# HIVE_BOARD_MCU.net
KiCad netlist of a schematic drawn in Altium Designer
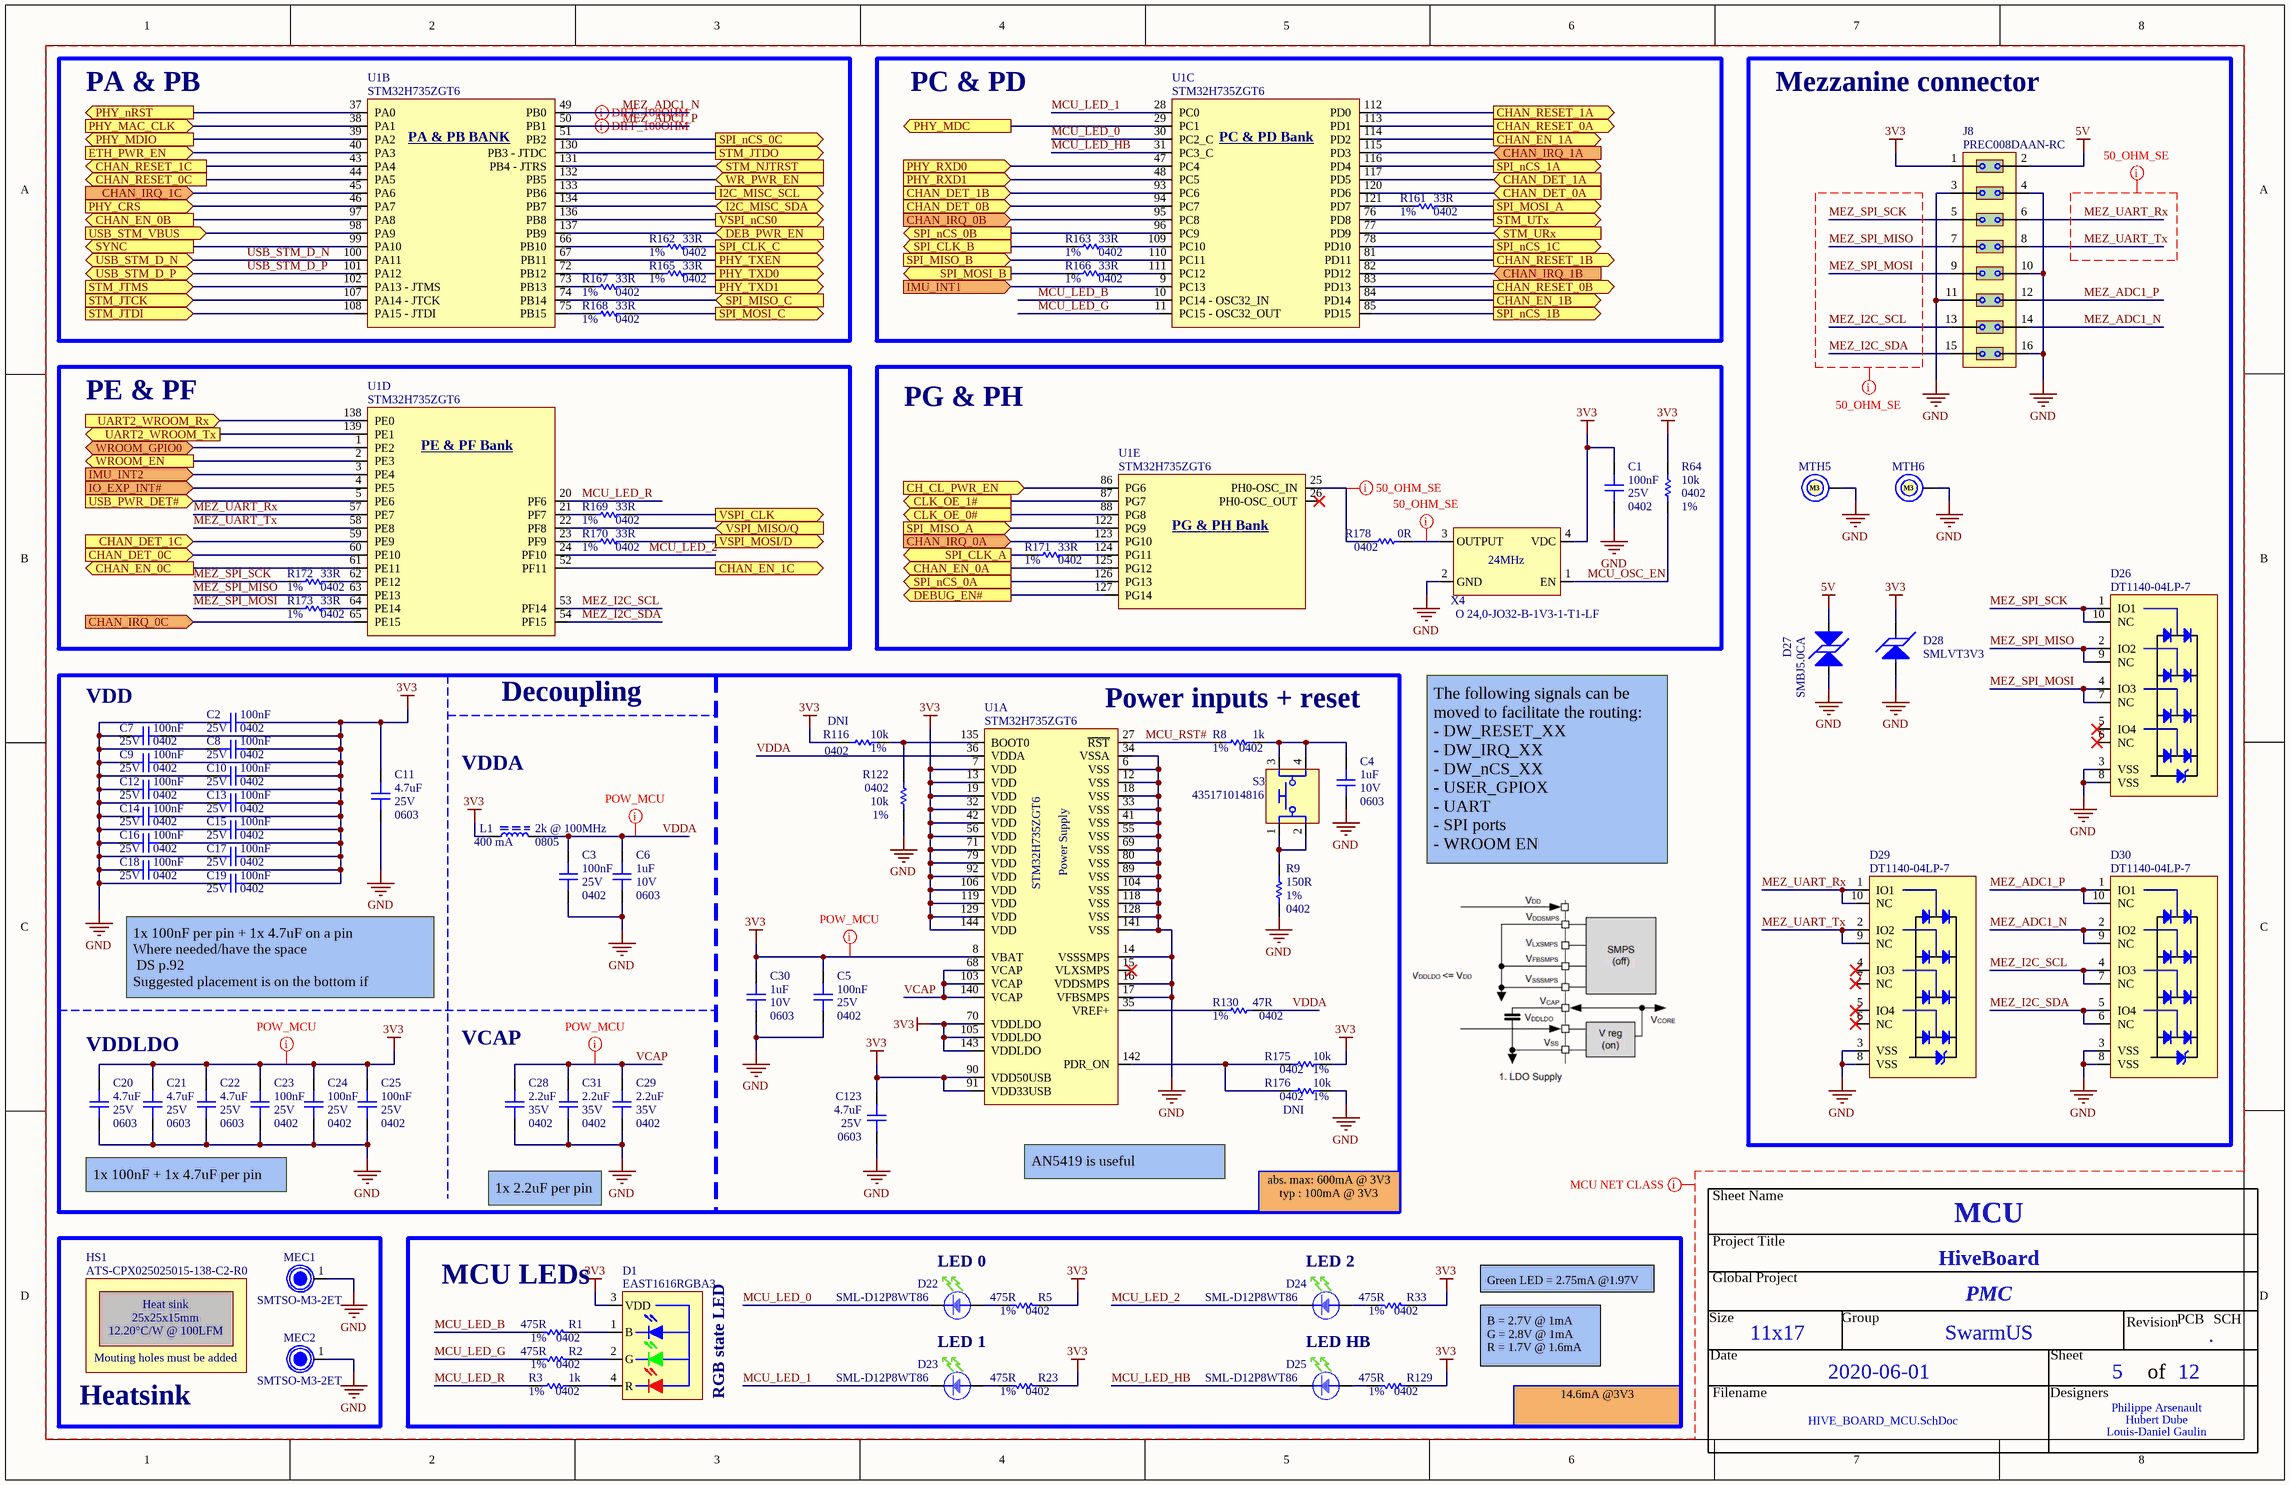
[diagram p0: HIVE_BOARD_MCU.SchDoc]

(export (version "E")
  (design (tool "Eeschema 10.0.6"))
  (components
    (comp (ref "C1")
      (value "100nF")
      (footprint "CAP_CER_0402")
      (description "CAP - CER 0.1µF 10% 25V X7R - 0402")
      (fields
        (field (name "TOLERANCE") "10%")
        (field (name "PACKAGE") "0402")
        (field (name "VOLTAGE RATING") "25V")
        (field (name "Comment") "CGA2B3X7R1E104K050BB")
        (field (name "CREATEDBY/DATE") "Nicolas Roy 2018-11-07")
        (field (name "VERIFIEDBY") "Nicolas V. (2019-01-22)")
      )
      (libsource (lib "GRAMS_MASTER_LIB") (part "CAP_CER_CGA2B3X7R1E104K050BB"))
    )
    (comp (ref "C2")
      (value "100nF")
      (footprint "CAP_CER_0402")
      (description "CAP - CER 0.1µF 10% 25V X7R - 0402")
      (fields
        (field (name "TOLERANCE") "10%")
        (field (name "PACKAGE") "0402")
        (field (name "VOLTAGE RATING") "25V")
        (field (name "Comment") "CGA2B3X7R1E104K050BB")
        (field (name "CREATEDBY/DATE") "Nicolas Roy 2018-11-07")
        (field (name "VERIFIEDBY") "Nicolas V. (2019-01-22)")
      )
      (libsource (lib "GRAMS_MASTER_LIB") (part "CAP_CER_CGA2B3X7R1E104K050BB"))
    )
    (comp (ref "C3")
      (value "100nF")
      (footprint "CAP_CER_0402")
      (description "CAP - CER 0.1µF 10% 25V X7R - 0402")
      (fields
        (field (name "TOLERANCE") "10%")
        (field (name "PACKAGE") "0402")
        (field (name "VOLTAGE RATING") "25V")
        (field (name "Comment") "CGA2B3X7R1E104K050BB")
        (field (name "CREATEDBY/DATE") "Nicolas Roy 2018-11-07")
        (field (name "VERIFIEDBY") "Nicolas V. (2019-01-22)")
      )
      (libsource (lib "GRAMS_MASTER_LIB") (part "CAP_CER_CGA2B3X7R1E104K050BB"))
    )
    (comp (ref "C4")
      (value "1uF")
      (footprint "CAP_CER_0603")
      (description "CAP - CER 1uF 10V 10% X5R - 0603")
      (fields
        (field (name "TOLERANCE") "10%")
        (field (name "PACKAGE") "0603")
        (field (name "VOLTAGE RATING") "10V")
        (field (name "Comment") "C0603C105K8PACTU")
        (field (name "CREATEDBY/DATE") "Hubert Dube - 21/07/20")
        (field (name "VERIFIEDBY") "Louis-Daniel Gaulin - 21/07/20")
      )
      (libsource (lib "SWARMUS_LIB") (part "CAP_CER_C0603C105K8PACTU"))
    )
    (comp (ref "C5")
      (value "100nF")
      (footprint "CAP_CER_0402")
      (description "CAP - CER 0.1µF 10% 25V X7R - 0402")
      (fields
        (field (name "TOLERANCE") "10%")
        (field (name "PACKAGE") "0402")
        (field (name "VOLTAGE RATING") "25V")
        (field (name "Comment") "CGA2B3X7R1E104K050BB")
        (field (name "CREATEDBY/DATE") "Nicolas Roy 2018-11-07")
        (field (name "VERIFIEDBY") "Nicolas V. (2019-01-22)")
      )
      (libsource (lib "GRAMS_MASTER_LIB") (part "CAP_CER_CGA2B3X7R1E104K050BB"))
    )
    (comp (ref "C6")
      (value "1uF")
      (footprint "CAP_CER_0603")
      (description "CAP - CER 1uF 10V 10% X5R - 0603")
      (fields
        (field (name "TOLERANCE") "10%")
        (field (name "PACKAGE") "0603")
        (field (name "VOLTAGE RATING") "10V")
        (field (name "Comment") "C0603C105K8PACTU")
        (field (name "CREATEDBY/DATE") "Hubert Dube - 21/07/20")
        (field (name "VERIFIEDBY") "Louis-Daniel Gaulin - 21/07/20")
      )
      (libsource (lib "SWARMUS_LIB") (part "CAP_CER_C0603C105K8PACTU"))
    )
    (comp (ref "C7")
      (value "100nF")
      (footprint "CAP_CER_0402")
      (description "CAP - CER 0.1µF 10% 25V X7R - 0402")
      (fields
        (field (name "TOLERANCE") "10%")
        (field (name "PACKAGE") "0402")
        (field (name "VOLTAGE RATING") "25V")
        (field (name "Comment") "CGA2B3X7R1E104K050BB")
        (field (name "CREATEDBY/DATE") "Nicolas Roy 2018-11-07")
        (field (name "VERIFIEDBY") "Nicolas V. (2019-01-22)")
      )
      (libsource (lib "GRAMS_MASTER_LIB") (part "CAP_CER_CGA2B3X7R1E104K050BB"))
    )
    (comp (ref "C8")
      (value "100nF")
      (footprint "CAP_CER_0402")
      (description "CAP - CER 0.1µF 10% 25V X7R - 0402")
      (fields
        (field (name "TOLERANCE") "10%")
        (field (name "PACKAGE") "0402")
        (field (name "VOLTAGE RATING") "25V")
        (field (name "Comment") "CGA2B3X7R1E104K050BB")
        (field (name "CREATEDBY/DATE") "Nicolas Roy 2018-11-07")
        (field (name "VERIFIEDBY") "Nicolas V. (2019-01-22)")
      )
      (libsource (lib "GRAMS_MASTER_LIB") (part "CAP_CER_CGA2B3X7R1E104K050BB"))
    )
    (comp (ref "C9")
      (value "100nF")
      (footprint "CAP_CER_0402")
      (description "CAP - CER 0.1µF 10% 25V X7R - 0402")
      (fields
        (field (name "TOLERANCE") "10%")
        (field (name "PACKAGE") "0402")
        (field (name "VOLTAGE RATING") "25V")
        (field (name "Comment") "CGA2B3X7R1E104K050BB")
        (field (name "CREATEDBY/DATE") "Nicolas Roy 2018-11-07")
        (field (name "VERIFIEDBY") "Nicolas V. (2019-01-22)")
      )
      (libsource (lib "GRAMS_MASTER_LIB") (part "CAP_CER_CGA2B3X7R1E104K050BB"))
    )
    (comp (ref "C10")
      (value "100nF")
      (footprint "CAP_CER_0402")
      (description "CAP - CER 0.1µF 10% 25V X7R - 0402")
      (fields
        (field (name "TOLERANCE") "10%")
        (field (name "PACKAGE") "0402")
        (field (name "VOLTAGE RATING") "25V")
        (field (name "Comment") "CGA2B3X7R1E104K050BB")
        (field (name "CREATEDBY/DATE") "Nicolas Roy 2018-11-07")
        (field (name "VERIFIEDBY") "Nicolas V. (2019-01-22)")
      )
      (libsource (lib "GRAMS_MASTER_LIB") (part "CAP_CER_CGA2B3X7R1E104K050BB"))
    )
    (comp (ref "C11")
      (value "4.7uF")
      (footprint "CAP_CER_0603")
      (description "CAP - CER 4.7µF 20% 25V X5R - 0603")
      (fields
        (field (name "TOLERANCE") "20%")
        (field (name "PACKAGE") "0603")
        (field (name "VOLTAGE RATING") "25V")
        (field (name "Comment") "CL10A475MA8NQNC")
        (field (name "CREATEDBY/DATE") "Nicolas Roy 2018-11-21")
        (field (name "VERIFIEDBY") "Nicolas V. (2019-01-22)")
      )
      (libsource (lib "GRAMS_MASTER_LIB") (part "CAP_CER_CL10A475MA8NQNC"))
    )
    (comp (ref "C12")
      (value "100nF")
      (footprint "CAP_CER_0402")
      (description "CAP - CER 0.1µF 10% 25V X7R - 0402")
      (fields
        (field (name "TOLERANCE") "10%")
        (field (name "PACKAGE") "0402")
        (field (name "VOLTAGE RATING") "25V")
        (field (name "Comment") "CGA2B3X7R1E104K050BB")
        (field (name "CREATEDBY/DATE") "Nicolas Roy 2018-11-07")
        (field (name "VERIFIEDBY") "Nicolas V. (2019-01-22)")
      )
      (libsource (lib "GRAMS_MASTER_LIB") (part "CAP_CER_CGA2B3X7R1E104K050BB"))
    )
    (comp (ref "C13")
      (value "100nF")
      (footprint "CAP_CER_0402")
      (description "CAP - CER 0.1µF 10% 25V X7R - 0402")
      (fields
        (field (name "TOLERANCE") "10%")
        (field (name "PACKAGE") "0402")
        (field (name "VOLTAGE RATING") "25V")
        (field (name "Comment") "CGA2B3X7R1E104K050BB")
        (field (name "CREATEDBY/DATE") "Nicolas Roy 2018-11-07")
        (field (name "VERIFIEDBY") "Nicolas V. (2019-01-22)")
      )
      (libsource (lib "GRAMS_MASTER_LIB") (part "CAP_CER_CGA2B3X7R1E104K050BB"))
    )
    (comp (ref "C14")
      (value "100nF")
      (footprint "CAP_CER_0402")
      (description "CAP - CER 0.1µF 10% 25V X7R - 0402")
      (fields
        (field (name "TOLERANCE") "10%")
        (field (name "PACKAGE") "0402")
        (field (name "VOLTAGE RATING") "25V")
        (field (name "Comment") "CGA2B3X7R1E104K050BB")
        (field (name "CREATEDBY/DATE") "Nicolas Roy 2018-11-07")
        (field (name "VERIFIEDBY") "Nicolas V. (2019-01-22)")
      )
      (libsource (lib "GRAMS_MASTER_LIB") (part "CAP_CER_CGA2B3X7R1E104K050BB"))
    )
    (comp (ref "C15")
      (value "100nF")
      (footprint "CAP_CER_0402")
      (description "CAP - CER 0.1µF 10% 25V X7R - 0402")
      (fields
        (field (name "TOLERANCE") "10%")
        (field (name "PACKAGE") "0402")
        (field (name "VOLTAGE RATING") "25V")
        (field (name "Comment") "CGA2B3X7R1E104K050BB")
        (field (name "CREATEDBY/DATE") "Nicolas Roy 2018-11-07")
        (field (name "VERIFIEDBY") "Nicolas V. (2019-01-22)")
      )
      (libsource (lib "GRAMS_MASTER_LIB") (part "CAP_CER_CGA2B3X7R1E104K050BB"))
    )
    (comp (ref "C16")
      (value "100nF")
      (footprint "CAP_CER_0402")
      (description "CAP - CER 0.1µF 10% 25V X7R - 0402")
      (fields
        (field (name "TOLERANCE") "10%")
        (field (name "PACKAGE") "0402")
        (field (name "VOLTAGE RATING") "25V")
        (field (name "Comment") "CGA2B3X7R1E104K050BB")
        (field (name "CREATEDBY/DATE") "Nicolas Roy 2018-11-07")
        (field (name "VERIFIEDBY") "Nicolas V. (2019-01-22)")
      )
      (libsource (lib "GRAMS_MASTER_LIB") (part "CAP_CER_CGA2B3X7R1E104K050BB"))
    )
    (comp (ref "C17")
      (value "100nF")
      (footprint "CAP_CER_0402")
      (description "CAP - CER 0.1µF 10% 25V X7R - 0402")
      (fields
        (field (name "TOLERANCE") "10%")
        (field (name "PACKAGE") "0402")
        (field (name "VOLTAGE RATING") "25V")
        (field (name "Comment") "CGA2B3X7R1E104K050BB")
        (field (name "CREATEDBY/DATE") "Nicolas Roy 2018-11-07")
        (field (name "VERIFIEDBY") "Nicolas V. (2019-01-22)")
      )
      (libsource (lib "GRAMS_MASTER_LIB") (part "CAP_CER_CGA2B3X7R1E104K050BB"))
    )
    (comp (ref "C18")
      (value "100nF")
      (footprint "CAP_CER_0402")
      (description "CAP - CER 0.1µF 10% 25V X7R - 0402")
      (fields
        (field (name "TOLERANCE") "10%")
        (field (name "PACKAGE") "0402")
        (field (name "VOLTAGE RATING") "25V")
        (field (name "Comment") "CGA2B3X7R1E104K050BB")
        (field (name "CREATEDBY/DATE") "Nicolas Roy 2018-11-07")
        (field (name "VERIFIEDBY") "Nicolas V. (2019-01-22)")
      )
      (libsource (lib "GRAMS_MASTER_LIB") (part "CAP_CER_CGA2B3X7R1E104K050BB"))
    )
    (comp (ref "C19")
      (value "100nF")
      (footprint "CAP_CER_0402")
      (description "CAP - CER 0.1µF 10% 25V X7R - 0402")
      (fields
        (field (name "TOLERANCE") "10%")
        (field (name "PACKAGE") "0402")
        (field (name "VOLTAGE RATING") "25V")
        (field (name "Comment") "CGA2B3X7R1E104K050BB")
        (field (name "CREATEDBY/DATE") "Nicolas Roy 2018-11-07")
        (field (name "VERIFIEDBY") "Nicolas V. (2019-01-22)")
      )
      (libsource (lib "GRAMS_MASTER_LIB") (part "CAP_CER_CGA2B3X7R1E104K050BB"))
    )
    (comp (ref "C20")
      (value "4.7uF")
      (footprint "CAP_CER_0603")
      (description "CAP - CER 4.7µF 20% 25V X5R - 0603")
      (fields
        (field (name "TOLERANCE") "20%")
        (field (name "PACKAGE") "0603")
        (field (name "VOLTAGE RATING") "25V")
        (field (name "Comment") "CL10A475MA8NQNC")
        (field (name "CREATEDBY/DATE") "Nicolas Roy 2018-11-21")
        (field (name "VERIFIEDBY") "Nicolas V. (2019-01-22)")
      )
      (libsource (lib "GRAMS_MASTER_LIB") (part "CAP_CER_CL10A475MA8NQNC"))
    )
    (comp (ref "C21")
      (value "4.7uF")
      (footprint "CAP_CER_0603")
      (description "CAP - CER 4.7µF 20% 25V X5R - 0603")
      (fields
        (field (name "TOLERANCE") "20%")
        (field (name "PACKAGE") "0603")
        (field (name "VOLTAGE RATING") "25V")
        (field (name "Comment") "CL10A475MA8NQNC")
        (field (name "CREATEDBY/DATE") "Nicolas Roy 2018-11-21")
        (field (name "VERIFIEDBY") "Nicolas V. (2019-01-22)")
      )
      (libsource (lib "GRAMS_MASTER_LIB") (part "CAP_CER_CL10A475MA8NQNC"))
    )
    (comp (ref "C22")
      (value "4.7uF")
      (footprint "CAP_CER_0603")
      (description "CAP - CER 4.7µF 20% 25V X5R - 0603")
      (fields
        (field (name "TOLERANCE") "20%")
        (field (name "PACKAGE") "0603")
        (field (name "VOLTAGE RATING") "25V")
        (field (name "Comment") "CL10A475MA8NQNC")
        (field (name "CREATEDBY/DATE") "Nicolas Roy 2018-11-21")
        (field (name "VERIFIEDBY") "Nicolas V. (2019-01-22)")
      )
      (libsource (lib "GRAMS_MASTER_LIB") (part "CAP_CER_CL10A475MA8NQNC"))
    )
    (comp (ref "C23")
      (value "100nF")
      (footprint "CAP_CER_0402")
      (description "CAP - CER 0.1µF 10% 25V X7R - 0402")
      (fields
        (field (name "TOLERANCE") "10%")
        (field (name "PACKAGE") "0402")
        (field (name "VOLTAGE RATING") "25V")
        (field (name "Comment") "CGA2B3X7R1E104K050BB")
        (field (name "CREATEDBY/DATE") "Nicolas Roy 2018-11-07")
        (field (name "VERIFIEDBY") "Nicolas V. (2019-01-22)")
      )
      (libsource (lib "GRAMS_MASTER_LIB") (part "CAP_CER_CGA2B3X7R1E104K050BB"))
    )
    (comp (ref "C24")
      (value "100nF")
      (footprint "CAP_CER_0402")
      (description "CAP - CER 0.1µF 10% 25V X7R - 0402")
      (fields
        (field (name "TOLERANCE") "10%")
        (field (name "PACKAGE") "0402")
        (field (name "VOLTAGE RATING") "25V")
        (field (name "Comment") "CGA2B3X7R1E104K050BB")
        (field (name "CREATEDBY/DATE") "Nicolas Roy 2018-11-07")
        (field (name "VERIFIEDBY") "Nicolas V. (2019-01-22)")
      )
      (libsource (lib "GRAMS_MASTER_LIB") (part "CAP_CER_CGA2B3X7R1E104K050BB"))
    )
    (comp (ref "C25")
      (value "100nF")
      (footprint "CAP_CER_0402")
      (description "CAP - CER 0.1µF 10% 25V X7R - 0402")
      (fields
        (field (name "TOLERANCE") "10%")
        (field (name "PACKAGE") "0402")
        (field (name "VOLTAGE RATING") "25V")
        (field (name "Comment") "CGA2B3X7R1E104K050BB")
        (field (name "CREATEDBY/DATE") "Nicolas Roy 2018-11-07")
        (field (name "VERIFIEDBY") "Nicolas V. (2019-01-22)")
      )
      (libsource (lib "GRAMS_MASTER_LIB") (part "CAP_CER_CGA2B3X7R1E104K050BB"))
    )
    (comp (ref "C28")
      (value "2.2uF")
      (footprint "CAP_CER_0402")
      (description "CAP - CER 2.2µF 10% 35V X5R - 0402")
      (fields
        (field (name "TOLERANCE") "10%")
        (field (name "PACKAGE") "0402")
        (field (name "VOLTAGE RATING") "35V")
        (field (name "Comment") "C1005X5R1V225K050BC")
        (field (name "CREATEDBY/DATE") "Nicolas Roy 2018-10-17")
        (field (name "VERIFIEDBY") "Caroline Paulin - 18 janv 2018")
      )
      (libsource (lib "GRAMS_MASTER_LIB") (part "CAP_CER_C1005X5R1V225K050BC"))
    )
    (comp (ref "C29")
      (value "2.2uF")
      (footprint "CAP_CER_0402")
      (description "CAP - CER 2.2µF 10% 35V X5R - 0402")
      (fields
        (field (name "TOLERANCE") "10%")
        (field (name "PACKAGE") "0402")
        (field (name "VOLTAGE RATING") "35V")
        (field (name "Comment") "C1005X5R1V225K050BC")
        (field (name "CREATEDBY/DATE") "Nicolas Roy 2018-10-17")
        (field (name "VERIFIEDBY") "Caroline Paulin - 18 janv 2018")
      )
      (libsource (lib "GRAMS_MASTER_LIB") (part "CAP_CER_C1005X5R1V225K050BC"))
    )
    (comp (ref "C30")
      (value "1uF")
      (footprint "CAP_CER_0603")
      (description "CAP - CER 1uF 10V 10% X5R - 0603")
      (fields
        (field (name "TOLERANCE") "10%")
        (field (name "PACKAGE") "0603")
        (field (name "VOLTAGE RATING") "10V")
        (field (name "Comment") "C0603C105K8PACTU")
        (field (name "CREATEDBY/DATE") "Hubert Dube - 21/07/20")
        (field (name "VERIFIEDBY") "Louis-Daniel Gaulin - 21/07/20")
      )
      (libsource (lib "SWARMUS_LIB") (part "CAP_CER_C0603C105K8PACTU"))
    )
    (comp (ref "C31")
      (value "2.2uF")
      (footprint "CAP_CER_0402")
      (description "CAP - CER 2.2µF 10% 35V X5R - 0402")
      (fields
        (field (name "TOLERANCE") "10%")
        (field (name "PACKAGE") "0402")
        (field (name "VOLTAGE RATING") "35V")
        (field (name "Comment") "C1005X5R1V225K050BC")
        (field (name "CREATEDBY/DATE") "Nicolas Roy 2018-10-17")
        (field (name "VERIFIEDBY") "Caroline Paulin - 18 janv 2018")
      )
      (libsource (lib "GRAMS_MASTER_LIB") (part "CAP_CER_C1005X5R1V225K050BC"))
    )
    (comp (ref "C123")
      (value "4.7uF")
      (footprint "CAP_CER_0603")
      (description "CAP - CER 4.7µF 20% 25V X5R - 0603")
      (fields
        (field (name "TOLERANCE") "20%")
        (field (name "PACKAGE") "0603")
        (field (name "VOLTAGE RATING") "25V")
        (field (name "Comment") "CL10A475MA8NQNC")
        (field (name "CREATEDBY/DATE") "Nicolas Roy 2018-11-21")
        (field (name "VERIFIEDBY") "Nicolas V. (2019-01-22)")
      )
      (libsource (lib "GRAMS_MASTER_LIB") (part "CAP_CER_CL10A475MA8NQNC"))
    )
    (comp (ref "D1")
      (value "EAST1616RGBA3")
      (footprint "DIO_EAST1616RGBA3")
      (fields
        (field (name "TOLERANCE") "±50ppm")
        (field (name "CREATEDBY/DATE") "Hubert Dube - 26/02/2021")
        (field (name "VERIFIEDBY") "PA + Hubert Dube - 19/03/2021")
      )
      (libsource (lib "SWARMUS_LIB") (part "DIO_EAST1616RGBA3"))
    )
    (comp (ref "D22")
      (value "SML-D12P8WT86")
      (footprint "LED_SML-D12P8WT86")
      (description "LED - GREEN DIFFUSED 0603 SMD - 0603")
      (fields
        (field (name "CREATEDBY/DATE") "Keven Deslandes - 2018/11/21")
        (field (name "VERIFIEDBY") "Caroline Paulin - 13 février 2019")
      )
      (libsource (lib "GRAMS_MASTER_LIB") (part "LED_SML-D12P8WT86"))
    )
    (comp (ref "D23")
      (value "SML-D12P8WT86")
      (footprint "LED_SML-D12P8WT86")
      (description "LED - GREEN DIFFUSED 0603 SMD - 0603")
      (fields
        (field (name "CREATEDBY/DATE") "Keven Deslandes - 2018/11/21")
        (field (name "VERIFIEDBY") "Caroline Paulin - 13 février 2019")
      )
      (libsource (lib "GRAMS_MASTER_LIB") (part "LED_SML-D12P8WT86"))
    )
    (comp (ref "D24")
      (value "SML-D12P8WT86")
      (footprint "LED_SML-D12P8WT86")
      (description "LED - GREEN DIFFUSED 0603 SMD - 0603")
      (fields
        (field (name "CREATEDBY/DATE") "Keven Deslandes - 2018/11/21")
        (field (name "VERIFIEDBY") "Caroline Paulin - 13 février 2019")
      )
      (libsource (lib "GRAMS_MASTER_LIB") (part "LED_SML-D12P8WT86"))
    )
    (comp (ref "D25")
      (value "SML-D12P8WT86")
      (footprint "LED_SML-D12P8WT86")
      (description "LED - GREEN DIFFUSED 0603 SMD - 0603")
      (fields
        (field (name "CREATEDBY/DATE") "Keven Deslandes - 2018/11/21")
        (field (name "VERIFIEDBY") "Caroline Paulin - 13 février 2019")
      )
      (libsource (lib "GRAMS_MASTER_LIB") (part "LED_SML-D12P8WT86"))
    )
    (comp (ref "D26")
      (value "DT1140-04LP-7")
      (footprint "TVS_DATA_DT1140-04LP-7")
      (description "TVS - DIODE 5.5V 10V - 10-UFDFN")
      (fields
        (field (name "CREATEDBY/DATE") "Joël Lemay 2019-11-20")
        (field (name "VERIFIEDBY") "C.Paulin - 21/11/2019")
      )
      (libsource (lib "GRAMS_MASTER_LIB") (part "TVS_DATA_DT1140-04LP-7"))
    )
    (comp (ref "D27")
      (value "SMBJ5.0CA")
      (footprint "TVS_PWR_SMBJ5.0CA")
      (description "TVS - BIDIR 5V 9.2V 600W - DO214AA")
      (fields
        (field (name "CREATEDBY/DATE") "Jonathan Bouchard - 2019-03-22")
        (field (name "VERIFIEDBY") "Nicolas V. (2019-05-06)")
      )
      (libsource (lib "GRAMS_MASTER_LIB") (part "TVS_PWR_SMBJ5.0CA"))
    )
    (comp (ref "D28")
      (value "SMLVT3V3")
      (footprint "TVS_POW_SMLVT3V3")
      (description "TVS - 3.3V 10.3V 600W - DO214AA")
      (fields
        (field (name "CREATEDBY/DATE") "Jonathan Bouchard - 2019-04-27")
        (field (name "VERIFIEDBY") "Nicolas V. (2019-05-06)")
      )
      (libsource (lib "GRAMS_MASTER_LIB") (part "TVS_POW_SMLVT3V3"))
    )
    (comp (ref "D29")
      (value "DT1140-04LP-7")
      (footprint "TVS_DATA_DT1140-04LP-7")
      (description "TVS - DIODE 5.5V 10V - 10-UFDFN")
      (fields
        (field (name "CREATEDBY/DATE") "Joël Lemay 2019-11-20")
        (field (name "VERIFIEDBY") "C.Paulin - 21/11/2019")
      )
      (libsource (lib "GRAMS_MASTER_LIB") (part "TVS_DATA_DT1140-04LP-7"))
    )
    (comp (ref "D30")
      (value "DT1140-04LP-7")
      (footprint "TVS_DATA_DT1140-04LP-7")
      (description "TVS - DIODE 5.5V 10V - 10-UFDFN")
      (fields
        (field (name "CREATEDBY/DATE") "Joël Lemay 2019-11-20")
        (field (name "VERIFIEDBY") "C.Paulin - 21/11/2019")
      )
      (libsource (lib "GRAMS_MASTER_LIB") (part "TVS_DATA_DT1140-04LP-7"))
    )
    (comp (ref "HS1")
      (value "ATS-CPX025025015-138-C2-R0")
      (footprint "THE_HS_ATS-CPX025025015-138-C2-R0_NOMH")
      (description "THE_HS - Heat Sink  25x25x15 mm - TH M3")
      (fields
        (field (name "CREATEDBY/DATE") "Philippe Arsenault/2021-04-08")
        (field (name "VERIFIEDBY") "Louis-Daniel Gaulin / 14-04-2021")
      )
      (libsource (lib "SWARMUS_LIB") (part "THE_HS_ATS-CPX025025015-138-C2-R0_NOMH"))
    )
    (comp (ref "J8")
      (value "PREC008DAAN-RC")
      (footprint "CON_HDR_PREC008DAAN-RC")
      (description "CON - Connector Header Through Hole 16 position 0.100\" (2.54mm)")
      (fields
        (field (name "VERIFIEDBY") "Philippe Arsenault/2021-03-25")
        (field (name "CREATEDBY/DATE") "Hubert Dube -  16/03/2021")
      )
      (libsource (lib "SWARMUS_LIB") (part "CON_HDR_PREC008DAAN-RC"))
    )
    (comp (ref "L1")
      (value "2k @ 100MHz")
      (footprint "FER_0805")
      (description "FER - FERRITE BEAD 2 KOHM @ 100 MHz 400 mA - 0805")
      (fields
        (field (name "CURRENT RATING") "400 mA")
        (field (name "PACKAGE") "0805")
        (field (name "Comment") "MMZ2012Y202BT000")
        (field (name "CREATEDBY/DATE") "Hubert Dube - 7/02/2021")
        (field (name "VERIFIEDBY") "Philippe Arsenault/ 2021-03-13")
      )
      (libsource (lib "SWARMUS_LIB") (part "FER_MMZ2012Y202BT000"))
    )
    (comp (ref "MEC1")
      (value "SMTSO-M3-2ET")
      (footprint "MEC_PEM_SMTSO-M3-2ET")
      (description "MEC- PEM SMD THREADED SPACER M3 - SMD")
      (fields
        (field (name "CREATEDBY/DATE") "Gabriel St-H./30-04-2019")
        (field (name "VERIFIEDBY") "Nicolas V. (2019-05-02)")
      )
      (libsource (lib "GRAMS_MASTER_LIB") (part "MEC_PEM_SMTSO-M3-2ET"))
    )
    (comp (ref "MEC2")
      (value "SMTSO-M3-2ET")
      (footprint "MEC_PEM_SMTSO-M3-2ET")
      (description "MEC- PEM SMD THREADED SPACER M3 - SMD")
      (fields
        (field (name "CREATEDBY/DATE") "Gabriel St-H./30-04-2019")
        (field (name "VERIFIEDBY") "Nicolas V. (2019-05-02)")
      )
      (libsource (lib "GRAMS_MASTER_LIB") (part "MEC_PEM_SMTSO-M3-2ET"))
    )
    (comp (ref "MTH5")
      (value "M3")
      (footprint "MTH_M3")
      (description "MTH - MOUNTING HOLE M3 PLATED - M3")
      (fields
        (field (name "CREATEDBY/DATE") "Jonathan Bouchard 2018-07-23")
        (field (name "VERIFIEDBY") "Arnaud Samson 23-07-18")
      )
      (libsource (lib "GRAMS_MASTER_LIB") (part "MTH_M3"))
    )
    (comp (ref "MTH6")
      (value "M3")
      (footprint "MTH_M3")
      (description "MTH - MOUNTING HOLE M3 PLATED - M3")
      (fields
        (field (name "CREATEDBY/DATE") "Jonathan Bouchard 2018-07-23")
        (field (name "VERIFIEDBY") "Arnaud Samson 23-07-18")
      )
      (libsource (lib "GRAMS_MASTER_LIB") (part "MTH_M3"))
    )
    (comp (ref "R1")
      (value "475R")
      (footprint "RES_0402")
      (description "RES - 475R 1% 1/10W- 0402")
      (fields
        (field (name "TOLERANCE") "1%")
        (field (name "PACKAGE") "0402")
        (field (name "Comment") "ERJ-2RKF4750X")
        (field (name "CREATEDBY/DATE") "Keven Deslandes 2018-10-17")
        (field (name "VERIFIEDBY") "Carolilne Paulin - 18/12/2018")
      )
      (libsource (lib "GRAMS_MASTER_LIB") (part "RES_ERJ-2RKF4750X"))
    )
    (comp (ref "R2")
      (value "475R")
      (footprint "RES_0402")
      (description "RES - 475R 1% 1/10W- 0402")
      (fields
        (field (name "TOLERANCE") "1%")
        (field (name "PACKAGE") "0402")
        (field (name "Comment") "ERJ-2RKF4750X")
        (field (name "CREATEDBY/DATE") "Keven Deslandes 2018-10-17")
        (field (name "VERIFIEDBY") "Carolilne Paulin - 18/12/2018")
      )
      (libsource (lib "GRAMS_MASTER_LIB") (part "RES_ERJ-2RKF4750X"))
    )
    (comp (ref "R3")
      (value "1k")
      (footprint "RES_0402")
      (description "RES - 1K OHM 1% 1/16W - 0402")
      (fields
        (field (name "TOLERANCE") "1%")
        (field (name "PACKAGE") "0402")
        (field (name "Comment") "RC0402FR-071KL")
        (field (name "CREATEDBY/DATE") "Jonathan Bouchard 2018-07-05")
        (field (name "VERIFIEDBY") "Arnaud Samson 16-07-18")
      )
      (libsource (lib "GRAMS_MASTER_LIB") (part "RES_RC0402FR-071KL"))
    )
    (comp (ref "R5")
      (value "475R")
      (footprint "RES_0402")
      (description "RES - 475R 1% 1/10W- 0402")
      (fields
        (field (name "TOLERANCE") "1%")
        (field (name "PACKAGE") "0402")
        (field (name "Comment") "ERJ-2RKF4750X")
        (field (name "CREATEDBY/DATE") "Keven Deslandes 2018-10-17")
        (field (name "VERIFIEDBY") "Carolilne Paulin - 18/12/2018")
      )
      (libsource (lib "GRAMS_MASTER_LIB") (part "RES_ERJ-2RKF4750X"))
    )
    (comp (ref "R8")
      (value "1k")
      (footprint "RES_0402")
      (description "RES - 1K OHM 1% 1/16W - 0402")
      (fields
        (field (name "TOLERANCE") "1%")
        (field (name "PACKAGE") "0402")
        (field (name "Comment") "RC0402FR-071KL")
        (field (name "CREATEDBY/DATE") "Jonathan Bouchard 2018-07-05")
        (field (name "VERIFIEDBY") "Arnaud Samson 16-07-18")
      )
      (libsource (lib "GRAMS_MASTER_LIB") (part "RES_RC0402FR-071KL"))
    )
    (comp (ref "R9")
      (value "150R")
      (footprint "RES_0402")
      (description "RES - 150R 1% 1/16W - 0402")
      (fields
        (field (name "TOLERANCE") "1%")
        (field (name "PACKAGE") "0402")
        (field (name "Comment") "RC0402FR-07150RL")
        (field (name "CREATEDBY/DATE") "Jonathan Bouchard 2019-03-25")
        (field (name "VERIFIEDBY") "Nicolas V. (2019-05-02)")
      )
      (libsource (lib "GRAMS_MASTER_LIB") (part "RES_RC0402FR-07150RL"))
    )
    (comp (ref "R23")
      (value "475R")
      (footprint "RES_0402")
      (description "RES - 475R 1% 1/10W- 0402")
      (fields
        (field (name "TOLERANCE") "1%")
        (field (name "PACKAGE") "0402")
        (field (name "Comment") "ERJ-2RKF4750X")
        (field (name "CREATEDBY/DATE") "Keven Deslandes 2018-10-17")
        (field (name "VERIFIEDBY") "Carolilne Paulin - 18/12/2018")
      )
      (libsource (lib "GRAMS_MASTER_LIB") (part "RES_ERJ-2RKF4750X"))
    )
    (comp (ref "R33")
      (value "475R")
      (footprint "RES_0402")
      (description "RES - 475R 1% 1/10W- 0402")
      (fields
        (field (name "TOLERANCE") "1%")
        (field (name "PACKAGE") "0402")
        (field (name "Comment") "ERJ-2RKF4750X")
        (field (name "CREATEDBY/DATE") "Keven Deslandes 2018-10-17")
        (field (name "VERIFIEDBY") "Carolilne Paulin - 18/12/2018")
      )
      (libsource (lib "GRAMS_MASTER_LIB") (part "RES_ERJ-2RKF4750X"))
    )
    (comp (ref "R64")
      (value "10k")
      (footprint "RES_0402")
      (description "RES - 10K OHMS 1% 1/16W - 0402")
      (fields
        (field (name "TOLERANCE") "1%")
        (field (name "PACKAGE") "0402")
        (field (name "Comment") "RC0402FR-0710KL")
        (field (name "CREATEDBY/DATE") "Nicolas V. (2018-11-20)")
        (field (name "VERIFIEDBY") "Nicolas V. (2018-11-20)")
      )
      (libsource (lib "GRAMS_MASTER_LIB") (part "RES_RC0402FR-0710KL"))
    )
    (comp (ref "R116")
      (value "10k")
      (footprint "RES_0402")
      (description "RES - 10K OHMS 1% 1/16W - 0402")
      (fields
        (field (name "TOLERANCE") "1%")
        (field (name "ASSEMBLY NOTE") "DNI")
        (field (name "PACKAGE") "0402")
        (field (name "Comment") "RC0402FR-0710KL")
        (field (name "CREATEDBY/DATE") "Nicolas V. (2018-11-20)")
        (field (name "VERIFIEDBY") "Nicolas V. (2018-11-20)")
      )
      (libsource (lib "GRAMS_MASTER_LIB") (part "RES_RC0402FR-0710KL"))
    )
    (comp (ref "R122")
      (value "10k")
      (footprint "RES_0402")
      (description "RES - 10K OHMS 1% 1/16W - 0402")
      (fields
        (field (name "TOLERANCE") "1%")
        (field (name "PACKAGE") "0402")
        (field (name "Comment") "RC0402FR-0710KL")
        (field (name "CREATEDBY/DATE") "Nicolas V. (2018-11-20)")
        (field (name "VERIFIEDBY") "Nicolas V. (2018-11-20)")
      )
      (libsource (lib "GRAMS_MASTER_LIB") (part "RES_RC0402FR-0710KL"))
    )
    (comp (ref "R129")
      (value "475R")
      (footprint "RES_0402")
      (description "RES - 475R 1% 1/10W- 0402")
      (fields
        (field (name "TOLERANCE") "1%")
        (field (name "PACKAGE") "0402")
        (field (name "Comment") "ERJ-2RKF4750X")
        (field (name "CREATEDBY/DATE") "Keven Deslandes 2018-10-17")
        (field (name "VERIFIEDBY") "Carolilne Paulin - 18/12/2018")
      )
      (libsource (lib "GRAMS_MASTER_LIB") (part "RES_ERJ-2RKF4750X"))
    )
    (comp (ref "R130")
      (value "47R")
      (footprint "RES_0402")
      (description "RES -  47ohm ±1% 0.063W, 1/16W Chip Resistor 0402")
      (fields
        (field (name "TOLERANCE") "1%")
        (field (name "PACKAGE") "0402")
        (field (name "Comment") "RC0402FR-0747RL")
        (field (name "CREATEDBY/DATE") "Philippe Arsenault/2021-04-10")
        (field (name "VERIFIEDBY") "Louis-Daniel Gaulin / 14-04-2021")
      )
      (libsource (lib "SWARMUS_LIB") (part "RES_RC0402FR-0747RL"))
    )
    (comp (ref "R161")
      (value "33R")
      (footprint "RES_0402")
      (description "RES - 33 OHM 1% 1/16W - 0402")
      (fields
        (field (name "TOLERANCE") "1%")
        (field (name "PACKAGE") "0402")
        (field (name "Comment") "RC0402FR-0733RL")
        (field (name "CREATEDBY/DATE") "Louis-Daniel Gaulin/ 14/01/2020")
        (field (name "VERIFIEDBY") "C.Paulin - 21/01/2020")
      )
      (libsource (lib "GRAMS_MASTER_LIB") (part "RES_RC0402FR-0733RL"))
    )
    (comp (ref "R162")
      (value "33R")
      (footprint "RES_0402")
      (description "RES - 33 OHM 1% 1/16W - 0402")
      (fields
        (field (name "TOLERANCE") "1%")
        (field (name "PACKAGE") "0402")
        (field (name "Comment") "RC0402FR-0733RL")
        (field (name "CREATEDBY/DATE") "Louis-Daniel Gaulin/ 14/01/2020")
        (field (name "VERIFIEDBY") "C.Paulin - 21/01/2020")
      )
      (libsource (lib "GRAMS_MASTER_LIB") (part "RES_RC0402FR-0733RL"))
    )
    (comp (ref "R163")
      (value "33R")
      (footprint "RES_0402")
      (description "RES - 33 OHM 1% 1/16W - 0402")
      (fields
        (field (name "TOLERANCE") "1%")
        (field (name "PACKAGE") "0402")
        (field (name "Comment") "RC0402FR-0733RL")
        (field (name "CREATEDBY/DATE") "Louis-Daniel Gaulin/ 14/01/2020")
        (field (name "VERIFIEDBY") "C.Paulin - 21/01/2020")
      )
      (libsource (lib "GRAMS_MASTER_LIB") (part "RES_RC0402FR-0733RL"))
    )
    (comp (ref "R165")
      (value "33R")
      (footprint "RES_0402")
      (description "RES - 33 OHM 1% 1/16W - 0402")
      (fields
        (field (name "TOLERANCE") "1%")
        (field (name "PACKAGE") "0402")
        (field (name "Comment") "RC0402FR-0733RL")
        (field (name "CREATEDBY/DATE") "Louis-Daniel Gaulin/ 14/01/2020")
        (field (name "VERIFIEDBY") "C.Paulin - 21/01/2020")
      )
      (libsource (lib "GRAMS_MASTER_LIB") (part "RES_RC0402FR-0733RL"))
    )
    (comp (ref "R166")
      (value "33R")
      (footprint "RES_0402")
      (description "RES - 33 OHM 1% 1/16W - 0402")
      (fields
        (field (name "TOLERANCE") "1%")
        (field (name "PACKAGE") "0402")
        (field (name "Comment") "RC0402FR-0733RL")
        (field (name "CREATEDBY/DATE") "Louis-Daniel Gaulin/ 14/01/2020")
        (field (name "VERIFIEDBY") "C.Paulin - 21/01/2020")
      )
      (libsource (lib "GRAMS_MASTER_LIB") (part "RES_RC0402FR-0733RL"))
    )
    (comp (ref "R167")
      (value "33R")
      (footprint "RES_0402")
      (description "RES - 33 OHM 1% 1/16W - 0402")
      (fields
        (field (name "TOLERANCE") "1%")
        (field (name "PACKAGE") "0402")
        (field (name "Comment") "RC0402FR-0733RL")
        (field (name "CREATEDBY/DATE") "Louis-Daniel Gaulin/ 14/01/2020")
        (field (name "VERIFIEDBY") "C.Paulin - 21/01/2020")
      )
      (libsource (lib "GRAMS_MASTER_LIB") (part "RES_RC0402FR-0733RL"))
    )
    (comp (ref "R168")
      (value "33R")
      (footprint "RES_0402")
      (description "RES - 33 OHM 1% 1/16W - 0402")
      (fields
        (field (name "TOLERANCE") "1%")
        (field (name "PACKAGE") "0402")
        (field (name "Comment") "RC0402FR-0733RL")
        (field (name "CREATEDBY/DATE") "Louis-Daniel Gaulin/ 14/01/2020")
        (field (name "VERIFIEDBY") "C.Paulin - 21/01/2020")
      )
      (libsource (lib "GRAMS_MASTER_LIB") (part "RES_RC0402FR-0733RL"))
    )
    (comp (ref "R169")
      (value "33R")
      (footprint "RES_0402")
      (description "RES - 33 OHM 1% 1/16W - 0402")
      (fields
        (field (name "TOLERANCE") "1%")
        (field (name "PACKAGE") "0402")
        (field (name "Comment") "RC0402FR-0733RL")
        (field (name "CREATEDBY/DATE") "Louis-Daniel Gaulin/ 14/01/2020")
        (field (name "VERIFIEDBY") "C.Paulin - 21/01/2020")
      )
      (libsource (lib "GRAMS_MASTER_LIB") (part "RES_RC0402FR-0733RL"))
    )
    (comp (ref "R170")
      (value "33R")
      (footprint "RES_0402")
      (description "RES - 33 OHM 1% 1/16W - 0402")
      (fields
        (field (name "TOLERANCE") "1%")
        (field (name "PACKAGE") "0402")
        (field (name "Comment") "RC0402FR-0733RL")
        (field (name "CREATEDBY/DATE") "Louis-Daniel Gaulin/ 14/01/2020")
        (field (name "VERIFIEDBY") "C.Paulin - 21/01/2020")
      )
      (libsource (lib "GRAMS_MASTER_LIB") (part "RES_RC0402FR-0733RL"))
    )
    (comp (ref "R171")
      (value "33R")
      (footprint "RES_0402")
      (description "RES - 33 OHM 1% 1/16W - 0402")
      (fields
        (field (name "TOLERANCE") "1%")
        (field (name "PACKAGE") "0402")
        (field (name "Comment") "RC0402FR-0733RL")
        (field (name "CREATEDBY/DATE") "Louis-Daniel Gaulin/ 14/01/2020")
        (field (name "VERIFIEDBY") "C.Paulin - 21/01/2020")
      )
      (libsource (lib "GRAMS_MASTER_LIB") (part "RES_RC0402FR-0733RL"))
    )
    (comp (ref "R172")
      (value "33R")
      (footprint "RES_0402")
      (description "RES - 33 OHM 1% 1/16W - 0402")
      (fields
        (field (name "TOLERANCE") "1%")
        (field (name "PACKAGE") "0402")
        (field (name "Comment") "RC0402FR-0733RL")
        (field (name "CREATEDBY/DATE") "Louis-Daniel Gaulin/ 14/01/2020")
        (field (name "VERIFIEDBY") "C.Paulin - 21/01/2020")
      )
      (libsource (lib "GRAMS_MASTER_LIB") (part "RES_RC0402FR-0733RL"))
    )
    (comp (ref "R173")
      (value "33R")
      (footprint "RES_0402")
      (description "RES - 33 OHM 1% 1/16W - 0402")
      (fields
        (field (name "TOLERANCE") "1%")
        (field (name "PACKAGE") "0402")
        (field (name "Comment") "RC0402FR-0733RL")
        (field (name "CREATEDBY/DATE") "Louis-Daniel Gaulin/ 14/01/2020")
        (field (name "VERIFIEDBY") "C.Paulin - 21/01/2020")
      )
      (libsource (lib "GRAMS_MASTER_LIB") (part "RES_RC0402FR-0733RL"))
    )
    (comp (ref "R175")
      (value "10k")
      (footprint "RES_0402")
      (description "RES - 10K OHMS 1% 1/16W - 0402")
      (fields
        (field (name "TOLERANCE") "1%")
        (field (name "PACKAGE") "0402")
        (field (name "Comment") "RC0402FR-0710KL")
        (field (name "CREATEDBY/DATE") "Nicolas V. (2018-11-20)")
        (field (name "VERIFIEDBY") "Nicolas V. (2018-11-20)")
      )
      (libsource (lib "GRAMS_MASTER_LIB") (part "RES_RC0402FR-0710KL"))
    )
    (comp (ref "R176")
      (value "10k")
      (footprint "RES_0402")
      (description "RES - 10K OHMS 1% 1/16W - 0402")
      (fields
        (field (name "TOLERANCE") "1%")
        (field (name "ASSEMBLY NOTE") "DNI")
        (field (name "PACKAGE") "0402")
        (field (name "Comment") "RC0402FR-0710KL")
        (field (name "CREATEDBY/DATE") "Nicolas V. (2018-11-20)")
        (field (name "VERIFIEDBY") "Nicolas V. (2018-11-20)")
      )
      (libsource (lib "GRAMS_MASTER_LIB") (part "RES_RC0402FR-0710KL"))
    )
    (comp (ref "R178")
      (value "0R")
      (footprint "RES_0402")
      (description "RES - 0R 1/16W 1A  - 0402")
      (fields
        (field (name "PACKAGE") "0402")
        (field (name "Comment") "RC0402FR-070RL")
        (field (name "CREATEDBY/DATE") "Keven Deslandes 2018-09-12")
        (field (name "VERIFIEDBY") "Caroline Paulin - 27 fév 2019")
      )
      (libsource (lib "GRAMS_MASTER_LIB") (part "RES_RC0402FR-070RL"))
    )
    (comp (ref "S3")
      (value "435171014816")
      (footprint "SWI_TACT_435171014816")
      (description "SWI - SWITCH TACTILE SPST-NO 0.05A 12V -SMD")
      (fields
        (field (name "CREATEDBY/DATE") "Hubert Dube - 22/07/20")
        (field (name "VERIFIEDBY") "Louis-Daniel Gaulin / 12-11-2020")
      )
      (libsource (lib "SWARMUS_LIB") (part "SWI_TACT_435171014816"))
    )
    (comp (ref "U1")
      (value "STM32H735ZGT6")
      (footprint "MCU_STM32H735ZGT6")
      (fields
        (field (name "CREATEDBY/DATE") "Philippe Arsenault/2021-04-08")
        (field (name "VERIFIEDBY") "Louis-Daniel Gaulin / 08-04-2021")
      )
      (libsource (lib "SWARMUS_LIB") (part "MCU_STM32H735ZGT6"))
    )
    (comp (ref "X4")
      (value "O 24,0-JO32-B-1V3-1-T1-LF")
      (footprint "OSC_O 24,0-JO32-B-1V3-1-T1-LF")
      (description "OSC - 24MHz XO (Standard) LVCMOS Oscillator 1.8V ~ 3.3V Enable/Disable 4-SMD, No Lead")
      (fields
        (field (name "TOLERANCE") "±50ppm")
        (field (name "CREATEDBY/DATE") "Louis-Daniel Gaulin / 13-04-2021")
        (field (name "VERIFIEDBY") "Philippe Arsenault/2021-04-14")
      )
      (libsource (lib "SWARMUS_LIB") (part "OSC_O 24,0-JO32-B-1V3-1-T1-LF"))
    )
  )
  (nets
    (net (code "1") (name "/CHAN_DET_0A") (class "Default")
      (node (ref "U1") (pin "120") (pinfunction "PD6_120") (pintype "passive"))
    )
    (net (code "2") (name "/CHAN_DET_0B") (class "Default")
      (node (ref "U1") (pin "94") (pinfunction "PC7_94") (pintype "passive"))
    )
    (net (code "3") (name "/CHAN_DET_0C") (class "Default")
      (node (ref "U1") (pin "60") (pinfunction "PE10_60") (pintype "passive"))
    )
    (net (code "4") (name "/CHAN_DET_1A") (class "Default")
      (node (ref "U1") (pin "117") (pinfunction "PD5_117") (pintype "passive"))
    )
    (net (code "5") (name "/CHAN_DET_1B") (class "Default")
      (node (ref "U1") (pin "93") (pinfunction "PC6_93") (pintype "passive"))
    )
    (net (code "6") (name "/CHAN_DET_1C") (class "Default")
      (node (ref "U1") (pin "59") (pinfunction "PE9_59") (pintype "passive"))
    )
    (net (code "7") (name "/CHAN_EN_0A") (class "Default")
      (node (ref "U1") (pin "125") (pinfunction "PG12_125") (pintype "passive"))
    )
    (net (code "8") (name "/CHAN_EN_0B") (class "Default")
      (node (ref "U1") (pin "97") (pinfunction "PA8_97") (pintype "passive"))
    )
    (net (code "9") (name "/CHAN_EN_0C") (class "Default")
      (node (ref "U1") (pin "61") (pinfunction "PE11_61") (pintype "passive"))
    )
    (net (code "10") (name "/CHAN_EN_1A") (class "Default")
      (node (ref "U1") (pin "114") (pinfunction "PD2_114") (pintype "passive"))
    )
    (net (code "11") (name "/CHAN_EN_1B") (class "Default")
      (node (ref "U1") (pin "84") (pinfunction "PD14_84") (pintype "passive"))
    )
    (net (code "12") (name "/CHAN_EN_1C") (class "Default")
      (node (ref "U1") (pin "52") (pinfunction "PF11_52") (pintype "passive"))
    )
    (net (code "13") (name "/CHAN_IRQ_0A") (class "Default")
      (node (ref "U1") (pin "123") (pinfunction "PG10_123") (pintype "passive"))
    )
    (net (code "14") (name "/CHAN_IRQ_0B") (class "Default")
      (node (ref "U1") (pin "95") (pinfunction "PC8_95") (pintype "passive"))
    )
    (net (code "15") (name "/CHAN_IRQ_0C") (class "Default")
      (node (ref "U1") (pin "65") (pinfunction "PE15_65") (pintype "passive"))
    )
    (net (code "16") (name "/CHAN_IRQ_1A") (class "Default")
      (node (ref "U1") (pin "115") (pinfunction "PD3_115") (pintype "passive"))
    )
    (net (code "17") (name "/CHAN_IRQ_1B") (class "Default")
      (node (ref "U1") (pin "82") (pinfunction "PD12_82") (pintype "passive"))
    )
    (net (code "18") (name "/CHAN_IRQ_1C") (class "Default")
      (node (ref "U1") (pin "45") (pinfunction "PA6_45") (pintype "passive"))
    )
    (net (code "19") (name "/CHAN_RESET_0A") (class "Default")
      (node (ref "U1") (pin "113") (pinfunction "PD1_113") (pintype "passive"))
    )
    (net (code "20") (name "/CHAN_RESET_0B") (class "Default")
      (node (ref "U1") (pin "83") (pinfunction "PD13_83") (pintype "passive"))
    )
    (net (code "21") (name "/CHAN_RESET_0C") (class "Default")
      (node (ref "U1") (pin "44") (pinfunction "PA5_44") (pintype "passive"))
    )
    (net (code "22") (name "/CHAN_RESET_1A") (class "Default")
      (node (ref "U1") (pin "112") (pinfunction "PD0_112") (pintype "passive"))
    )
    (net (code "23") (name "/CHAN_RESET_1B") (class "Default")
      (node (ref "U1") (pin "81") (pinfunction "PD11_81") (pintype "passive"))
    )
    (net (code "24") (name "/CHAN_RESET_1C") (class "Default")
      (node (ref "U1") (pin "43") (pinfunction "PA4_43") (pintype "passive"))
    )
    (net (code "25") (name "/CH_CL_PWR_EN") (class "Default")
      (node (ref "U1") (pin "86") (pinfunction "PG6_86") (pintype "passive"))
    )
    (net (code "26") (name "/CLK_OE_0#") (class "Default")
      (node (ref "U1") (pin "88") (pinfunction "PG8_88") (pintype "passive"))
    )
    (net (code "27") (name "/CLK_OE_1#") (class "Default")
      (node (ref "U1") (pin "87") (pinfunction "PG7_87") (pintype "passive"))
    )
    (net (code "28") (name "/DEBUG_EN#") (class "Default")
      (node (ref "U1") (pin "127") (pinfunction "PG14_127") (pintype "passive"))
    )
    (net (code "29") (name "/DEB_PWR_EN") (class "Default")
      (node (ref "U1") (pin "137") (pinfunction "PB9_137") (pintype "passive"))
    )
    (net (code "30") (name "/ETH_PWR_EN") (class "Default")
      (node (ref "U1") (pin "40") (pinfunction "PA3_40") (pintype "passive"))
    )
    (net (code "31") (name "/I2C_MISC_SCL") (class "Default")
      (node (ref "U1") (pin "133") (pinfunction "PB6_133") (pintype "passive"))
    )
    (net (code "32") (name "/I2C_MISC_SDA") (class "Default")
      (node (ref "U1") (pin "134") (pinfunction "PB7_134") (pintype "passive"))
    )
    (net (code "33") (name "/IMU_INT1") (class "Default")
      (node (ref "U1") (pin "9") (pinfunction "PC13_9") (pintype "passive"))
    )
    (net (code "34") (name "/IMU_INT2") (class "Default")
      (node (ref "U1") (pin "3") (pinfunction "PE4_3") (pintype "passive"))
    )
    (net (code "35") (name "/IO_EXP_INT#") (class "Default")
      (node (ref "U1") (pin "4") (pinfunction "PE5_4") (pintype "passive"))
    )
    (net (code "36") (name "/MCU_LED_0") (class "Default")
      (node (ref "D22") (pin "K") (pinfunction "K_K") (pintype "passive"))
      (node (ref "U1") (pin "30") (pinfunction "PC2_C_30") (pintype "passive"))
    )
    (net (code "37") (name "/MCU_LED_1") (class "Default")
      (node (ref "D23") (pin "K") (pinfunction "K_K") (pintype "passive"))
      (node (ref "U1") (pin "28") (pinfunction "PC0_28") (pintype "passive"))
    )
    (net (code "38") (name "/MCU_LED_2") (class "Default")
      (node (ref "D24") (pin "K") (pinfunction "K_K") (pintype "passive"))
      (node (ref "U1") (pin "24") (pinfunction "PF10_24") (pintype "passive"))
    )
    (net (code "39") (name "/MCU_LED_B") (class "Default")
      (node (ref "R1") (pin "2") (pinfunction "2_2") (pintype "passive"))
      (node (ref "U1") (pin "10") (pinfunction "PC14_-_OSC32_IN_10") (pintype "passive"))
    )
    (net (code "40") (name "/MCU_LED_G") (class "Default")
      (node (ref "R2") (pin "2") (pinfunction "2_2") (pintype "passive"))
      (node (ref "U1") (pin "11") (pinfunction "PC15_-_OSC32_OUT_11") (pintype "passive"))
    )
    (net (code "41") (name "/MCU_LED_HB") (class "Default")
      (node (ref "D25") (pin "K") (pinfunction "K_K") (pintype "passive"))
      (node (ref "U1") (pin "31") (pinfunction "PC3_C_31") (pintype "passive"))
    )
    (net (code "42") (name "/MCU_LED_R") (class "Default")
      (node (ref "R3") (pin "2") (pinfunction "2_2") (pintype "passive"))
      (node (ref "U1") (pin "20") (pinfunction "PF6_20") (pintype "passive"))
    )
    (net (code "43") (name "/MCU_OSC_EN") (class "Default")
      (node (ref "R64") (pin "2") (pinfunction "2_2") (pintype "passive"))
      (node (ref "X4") (pin "1") (pinfunction "EN_1") (pintype "passive"))
    )
    (net (code "44") (name "/MCU_RST#") (class "Default")
      (node (ref "R8") (pin "2") (pinfunction "2_2") (pintype "passive"))
      (node (ref "U1") (pin "27") (pinfunction "RST_27") (pintype "passive"))
    )
    (net (code "45") (name "/MEZ_ADC1_N") (class "Default")
      (node (ref "D30") (pin "2") (pinfunction "IO2_2") (pintype "passive"))
      (node (ref "D30") (pin "9") (pinfunction "NC_9") (pintype "passive"))
      (node (ref "J8") (pin "14") (pintype "passive"))
      (node (ref "U1") (pin "49") (pinfunction "PB0_49") (pintype "passive"))
    )
    (net (code "46") (name "/MEZ_ADC1_P") (class "Default")
      (node (ref "D30") (pin "1") (pinfunction "IO1_1") (pintype "passive"))
      (node (ref "D30") (pin "10") (pinfunction "NC_10") (pintype "passive"))
      (node (ref "J8") (pin "12") (pintype "passive"))
      (node (ref "U1") (pin "50") (pinfunction "PB1_50") (pintype "passive"))
    )
    (net (code "47") (name "/MEZ_I2C_SCL") (class "Default")
      (node (ref "D30") (pin "4") (pinfunction "IO3_4") (pintype "passive"))
      (node (ref "D30") (pin "7") (pinfunction "NC_7") (pintype "passive"))
      (node (ref "J8") (pin "13") (pintype "passive"))
      (node (ref "U1") (pin "53") (pinfunction "PF14_53") (pintype "passive"))
    )
    (net (code "48") (name "/MEZ_I2C_SDA") (class "Default")
      (node (ref "D30") (pin "5") (pinfunction "IO4_5") (pintype "passive"))
      (node (ref "D30") (pin "6") (pinfunction "NC_6") (pintype "passive"))
      (node (ref "J8") (pin "15") (pintype "passive"))
      (node (ref "U1") (pin "54") (pinfunction "PF15_54") (pintype "passive"))
    )
    (net (code "49") (name "/MEZ_SPI_MISO") (class "Default")
      (node (ref "D26") (pin "2") (pinfunction "IO2_2") (pintype "passive"))
      (node (ref "D26") (pin "9") (pinfunction "NC_9") (pintype "passive"))
      (node (ref "J8") (pin "7") (pintype "passive"))
      (node (ref "U1") (pin "63") (pinfunction "PE13_63") (pintype "passive"))
    )
    (net (code "50") (name "/MEZ_SPI_MOSI") (class "Default")
      (node (ref "D26") (pin "4") (pinfunction "IO3_4") (pintype "passive"))
      (node (ref "D26") (pin "7") (pinfunction "NC_7") (pintype "passive"))
      (node (ref "J8") (pin "9") (pintype "passive"))
      (node (ref "R173") (pin "2") (pinfunction "2_2") (pintype "passive"))
    )
    (net (code "51") (name "/MEZ_SPI_SCK") (class "Default")
      (node (ref "D26") (pin "1") (pinfunction "IO1_1") (pintype "passive"))
      (node (ref "D26") (pin "10") (pinfunction "NC_10") (pintype "passive"))
      (node (ref "J8") (pin "5") (pintype "passive"))
      (node (ref "R172") (pin "2") (pinfunction "2_2") (pintype "passive"))
    )
    (net (code "52") (name "/MEZ_UART_Rx") (class "Default")
      (node (ref "D29") (pin "1") (pinfunction "IO1_1") (pintype "passive"))
      (node (ref "D29") (pin "10") (pinfunction "NC_10") (pintype "passive"))
      (node (ref "J8") (pin "6") (pintype "passive"))
      (node (ref "U1") (pin "57") (pinfunction "PE7_57") (pintype "passive"))
    )
    (net (code "53") (name "/MEZ_UART_Tx") (class "Default")
      (node (ref "D29") (pin "2") (pinfunction "IO2_2") (pintype "passive"))
      (node (ref "D29") (pin "9") (pinfunction "NC_9") (pintype "passive"))
      (node (ref "J8") (pin "8") (pintype "passive"))
      (node (ref "U1") (pin "58") (pinfunction "PE8_58") (pintype "passive"))
    )
    (net (code "54") (name "/PHY_CRS") (class "Default")
      (node (ref "U1") (pin "46") (pinfunction "PA7_46") (pintype "passive"))
    )
    (net (code "55") (name "/PHY_MAC_CLK") (class "Default")
      (node (ref "U1") (pin "38") (pinfunction "PA1_38") (pintype "passive"))
    )
    (net (code "56") (name "/PHY_MDC") (class "Default")
      (node (ref "U1") (pin "29") (pinfunction "PC1_29") (pintype "passive"))
    )
    (net (code "57") (name "/PHY_MDIO") (class "Default")
      (node (ref "U1") (pin "39") (pinfunction "PA2_39") (pintype "passive"))
    )
    (net (code "58") (name "/PHY_RXD0") (class "Default")
      (node (ref "U1") (pin "47") (pinfunction "PC4_47") (pintype "passive"))
    )
    (net (code "59") (name "/PHY_RXD1") (class "Default")
      (node (ref "U1") (pin "48") (pinfunction "PC5_48") (pintype "passive"))
    )
    (net (code "60") (name "/PHY_TXD0") (class "Default")
      (node (ref "R165") (pin "1") (pinfunction "1_1") (pintype "passive"))
    )
    (net (code "61") (name "/PHY_TXD1") (class "Default")
      (node (ref "R167") (pin "1") (pinfunction "1_1") (pintype "passive"))
    )
    (net (code "62") (name "/PHY_TXEN") (class "Default")
      (node (ref "U1") (pin "67") (pinfunction "PB11_67") (pintype "passive"))
    )
    (net (code "63") (name "/PHY_nRST") (class "Default")
      (node (ref "U1") (pin "37") (pinfunction "PA0_37") (pintype "passive"))
    )
    (net (code "64") (name "/SPI_CLK_A") (class "Default")
      (node (ref "R171") (pin "2") (pinfunction "2_2") (pintype "passive"))
    )
    (net (code "65") (name "/SPI_CLK_B") (class "Default")
      (node (ref "R163") (pin "2") (pinfunction "2_2") (pintype "passive"))
    )
    (net (code "66") (name "/SPI_CLK_C") (class "Default")
      (node (ref "R162") (pin "1") (pinfunction "1_1") (pintype "passive"))
    )
    (net (code "67") (name "/SPI_MISO_A") (class "Default")
      (node (ref "U1") (pin "122") (pinfunction "PG9_122") (pintype "passive"))
    )
    (net (code "68") (name "/SPI_MISO_B") (class "Default")
      (node (ref "U1") (pin "110") (pinfunction "PC11_110") (pintype "passive"))
    )
    (net (code "69") (name "/SPI_MISO_C") (class "Default")
      (node (ref "U1") (pin "74") (pinfunction "PB14_74") (pintype "passive"))
    )
    (net (code "70") (name "/SPI_MOSI_A") (class "Default")
      (node (ref "R161") (pin "1") (pinfunction "1_1") (pintype "passive"))
    )
    (net (code "71") (name "/SPI_MOSI_B") (class "Default")
      (node (ref "R166") (pin "2") (pinfunction "2_2") (pintype "passive"))
    )
    (net (code "72") (name "/SPI_MOSI_C") (class "Default")
      (node (ref "R168") (pin "1") (pinfunction "1_1") (pintype "passive"))
    )
    (net (code "73") (name "/SPI_nCS_0A") (class "Default")
      (node (ref "U1") (pin "126") (pinfunction "PG13_126") (pintype "passive"))
    )
    (net (code "74") (name "/SPI_nCS_0B") (class "Default")
      (node (ref "U1") (pin "96") (pinfunction "PC9_96") (pintype "passive"))
    )
    (net (code "75") (name "/SPI_nCS_0C") (class "Default")
      (node (ref "U1") (pin "51") (pinfunction "PB2_51") (pintype "passive"))
    )
    (net (code "76") (name "/SPI_nCS_1A") (class "Default")
      (node (ref "U1") (pin "116") (pinfunction "PD4_116") (pintype "passive"))
    )
    (net (code "77") (name "/SPI_nCS_1B") (class "Default")
      (node (ref "U1") (pin "85") (pinfunction "PD15_85") (pintype "passive"))
    )
    (net (code "78") (name "/SPI_nCS_1C") (class "Default")
      (node (ref "U1") (pin "78") (pinfunction "PD10_78") (pintype "passive"))
    )
    (net (code "79") (name "/STM_JTCK") (class "Default")
      (node (ref "U1") (pin "107") (pinfunction "PA14_-_JTCK_107") (pintype "passive"))
    )
    (net (code "80") (name "/STM_JTDI") (class "Default")
      (node (ref "U1") (pin "108") (pinfunction "PA15_-_JTDI_108") (pintype "passive"))
    )
    (net (code "81") (name "/STM_JTDO") (class "Default")
      (node (ref "U1") (pin "130") (pinfunction "PB3_-_JTDC_130") (pintype "passive"))
    )
    (net (code "82") (name "/STM_JTMS") (class "Default")
      (node (ref "U1") (pin "102") (pinfunction "PA13_-_JTMS_102") (pintype "passive"))
    )
    (net (code "83") (name "/STM_NJTRST") (class "Default")
      (node (ref "U1") (pin "131") (pinfunction "PB4_-_JTRS_131") (pintype "passive"))
    )
    (net (code "84") (name "/STM_URx") (class "Default")
      (node (ref "U1") (pin "77") (pinfunction "PD9_77") (pintype "passive"))
    )
    (net (code "85") (name "/STM_UTx") (class "Default")
      (node (ref "U1") (pin "76") (pinfunction "PD8_76") (pintype "passive"))
    )
    (net (code "86") (name "/SYNC") (class "Default")
      (node (ref "U1") (pin "99") (pinfunction "PA10_99") (pintype "passive"))
    )
    (net (code "87") (name "/UART2_WROOM_Rx") (class "Default")
      (node (ref "U1") (pin "138") (pinfunction "PE0_138") (pintype "passive"))
    )
    (net (code "88") (name "/UART2_WROOM_Tx") (class "Default")
      (node (ref "U1") (pin "139") (pinfunction "PE1_139") (pintype "passive"))
    )
    (net (code "89") (name "/USB_PWR_DET#") (class "Default")
      (node (ref "U1") (pin "5") (pinfunction "PE6_5") (pintype "passive"))
    )
    (net (code "90") (name "/USB_STM_D_N") (class "Default")
      (node (ref "U1") (pin "100") (pinfunction "PA11_100") (pintype "passive"))
    )
    (net (code "91") (name "/USB_STM_D_P") (class "Default")
      (node (ref "U1") (pin "101") (pinfunction "PA12_101") (pintype "passive"))
    )
    (net (code "92") (name "/USB_STM_VBUS") (class "Default")
      (node (ref "U1") (pin "98") (pinfunction "PA9_98") (pintype "passive"))
    )
    (net (code "93") (name "/VCAP") (class "Default")
      (node (ref "C28") (pin "2") (pinfunction "2_2") (pintype "passive"))
      (node (ref "C29") (pin "2") (pinfunction "2_2") (pintype "passive"))
      (node (ref "C31") (pin "2") (pinfunction "2_2") (pintype "passive"))
      (node (ref "U1") (pin "103") (pinfunction "VCAP_103") (pintype "passive"))
      (node (ref "U1") (pin "140") (pinfunction "VCAP_140") (pintype "passive"))
      (node (ref "U1") (pin "68") (pinfunction "VCAP_68") (pintype "passive"))
    )
    (net (code "94") (name "/VDDA") (class "Default")
      (node (ref "C3") (pin "2") (pinfunction "2_2") (pintype "passive"))
      (node (ref "C6") (pin "1") (pinfunction "1_1") (pintype "passive"))
      (node (ref "L1") (pin "2") (pinfunction "2_2") (pintype "passive"))
      (node (ref "R130") (pin "1") (pinfunction "1_1") (pintype "passive"))
      (node (ref "U1") (pin "36") (pinfunction "VDDA_36") (pintype "passive"))
    )
    (net (code "95") (name "/VSPI_CLK") (class "Default")
      (node (ref "R169") (pin "1") (pinfunction "1_1") (pintype "passive"))
    )
    (net (code "96") (name "/VSPI_MISO{slash}Q") (class "Default")
      (node (ref "U1") (pin "22") (pinfunction "PF8_22") (pintype "passive"))
    )
    (net (code "97") (name "/VSPI_MOSI{slash}D") (class "Default")
      (node (ref "R170") (pin "1") (pinfunction "1_1") (pintype "passive"))
    )
    (net (code "98") (name "/VSPI_nCS0") (class "Default")
      (node (ref "U1") (pin "136") (pinfunction "PB8_136") (pintype "passive"))
    )
    (net (code "99") (name "/WROOM_EN") (class "Default")
      (node (ref "U1") (pin "2") (pinfunction "PE3_2") (pintype "passive"))
    )
    (net (code "100") (name "/WROOM_GPIO0") (class "Default")
      (node (ref "U1") (pin "1") (pinfunction "PE2_1") (pintype "passive"))
    )
    (net (code "101") (name "/WR_PWR_EN") (class "Default")
      (node (ref "U1") (pin "132") (pinfunction "PB5_132") (pintype "passive"))
    )
    (net (code "102") (name "3V3") (class "Default")
      (node (ref "C1") (pin "2") (pinfunction "2_2") (pintype "passive"))
      (node (ref "C10") (pin "1") (pinfunction "1_1") (pintype "passive"))
      (node (ref "C11") (pin "2") (pinfunction "2_2") (pintype "passive"))
      (node (ref "C12") (pin "1") (pinfunction "1_1") (pintype "passive"))
      (node (ref "C123") (pin "2") (pinfunction "2_2") (pintype "passive"))
      (node (ref "C13") (pin "1") (pinfunction "1_1") (pintype "passive"))
      (node (ref "C14") (pin "1") (pinfunction "1_1") (pintype "passive"))
      (node (ref "C15") (pin "1") (pinfunction "1_1") (pintype "passive"))
      (node (ref "C16") (pin "1") (pinfunction "1_1") (pintype "passive"))
      (node (ref "C17") (pin "1") (pinfunction "1_1") (pintype "passive"))
      (node (ref "C18") (pin "1") (pinfunction "1_1") (pintype "passive"))
      (node (ref "C19") (pin "1") (pinfunction "1_1") (pintype "passive"))
      (node (ref "C2") (pin "1") (pinfunction "1_1") (pintype "passive"))
      (node (ref "C20") (pin "2") (pinfunction "2_2") (pintype "passive"))
      (node (ref "C21") (pin "2") (pinfunction "2_2") (pintype "passive"))
      (node (ref "C22") (pin "2") (pinfunction "2_2") (pintype "passive"))
      (node (ref "C23") (pin "2") (pinfunction "2_2") (pintype "passive"))
      (node (ref "C24") (pin "2") (pinfunction "2_2") (pintype "passive"))
      (node (ref "C25") (pin "2") (pinfunction "2_2") (pintype "passive"))
      (node (ref "C30") (pin "1") (pinfunction "1_1") (pintype "passive"))
      (node (ref "C5") (pin "2") (pinfunction "2_2") (pintype "passive"))
      (node (ref "C7") (pin "1") (pinfunction "1_1") (pintype "passive"))
      (node (ref "C8") (pin "1") (pinfunction "1_1") (pintype "passive"))
      (node (ref "C9") (pin "1") (pinfunction "1_1") (pintype "passive"))
      (node (ref "D1") (pin "3") (pinfunction "VDD_3") (pintype "passive"))
      (node (ref "D28") (pin "K") (pinfunction "K_K") (pintype "passive"))
      (node (ref "J8") (pin "1") (pintype "passive"))
      (node (ref "L1") (pin "1") (pinfunction "1_1") (pintype "passive"))
      (node (ref "R116") (pin "1") (pinfunction "1_1") (pintype "passive"))
      (node (ref "R129") (pin "1") (pinfunction "1_1") (pintype "passive"))
      (node (ref "R175") (pin "2") (pinfunction "2_2") (pintype "passive"))
      (node (ref "R23") (pin "1") (pinfunction "1_1") (pintype "passive"))
      (node (ref "R33") (pin "1") (pinfunction "1_1") (pintype "passive"))
      (node (ref "R5") (pin "1") (pinfunction "1_1") (pintype "passive"))
      (node (ref "R64") (pin "1") (pinfunction "1_1") (pintype "passive"))
      (node (ref "U1") (pin "105") (pinfunction "VDDLDO_105") (pintype "passive"))
      (node (ref "U1") (pin "106") (pinfunction "VDD_106") (pintype "passive"))
      (node (ref "U1") (pin "119") (pinfunction "VDD_119") (pintype "passive"))
      (node (ref "U1") (pin "129") (pinfunction "VDD_129") (pintype "passive"))
      (node (ref "U1") (pin "13") (pinfunction "VDD_13") (pintype "passive"))
      (node (ref "U1") (pin "143") (pinfunction "VDDLDO_143") (pintype "passive"))
      (node (ref "U1") (pin "144") (pinfunction "VDD_144") (pintype "passive"))
      (node (ref "U1") (pin "19") (pinfunction "VDD_19") (pintype "passive"))
      (node (ref "U1") (pin "32") (pinfunction "VDD_32") (pintype "passive"))
      (node (ref "U1") (pin "42") (pinfunction "VDD_42") (pintype "passive"))
      (node (ref "U1") (pin "56") (pinfunction "VDD_56") (pintype "passive"))
      (node (ref "U1") (pin "7") (pinfunction "VDD_7") (pintype "passive"))
      (node (ref "U1") (pin "70") (pinfunction "VDDLDO_70") (pintype "passive"))
      (node (ref "U1") (pin "71") (pinfunction "VDD_71") (pintype "passive"))
      (node (ref "U1") (pin "79") (pinfunction "VDD_79") (pintype "passive"))
      (node (ref "U1") (pin "8") (pinfunction "VBAT_8") (pintype "passive"))
      (node (ref "U1") (pin "90") (pinfunction "VDD50USB_90") (pintype "passive"))
      (node (ref "U1") (pin "91") (pinfunction "VDD33USB_91") (pintype "passive"))
      (node (ref "U1") (pin "92") (pinfunction "VDD_92") (pintype "passive"))
      (node (ref "X4") (pin "4") (pinfunction "VDC_4") (pintype "passive"))
    )
    (net (code "103") (name "5V") (class "Default")
      (node (ref "D27") (pin "1") (pinfunction "1_1") (pintype "passive"))
      (node (ref "J8") (pin "2") (pintype "passive"))
    )
    (net (code "104") (name "GND") (class "Default")
      (node (ref "C1") (pin "1") (pinfunction "1_1") (pintype "passive"))
      (node (ref "C10") (pin "2") (pinfunction "2_2") (pintype "passive"))
      (node (ref "C11") (pin "1") (pinfunction "1_1") (pintype "passive"))
      (node (ref "C12") (pin "2") (pinfunction "2_2") (pintype "passive"))
      (node (ref "C123") (pin "1") (pinfunction "1_1") (pintype "passive"))
      (node (ref "C13") (pin "2") (pinfunction "2_2") (pintype "passive"))
      (node (ref "C14") (pin "2") (pinfunction "2_2") (pintype "passive"))
      (node (ref "C15") (pin "2") (pinfunction "2_2") (pintype "passive"))
      (node (ref "C16") (pin "2") (pinfunction "2_2") (pintype "passive"))
      (node (ref "C17") (pin "2") (pinfunction "2_2") (pintype "passive"))
      (node (ref "C18") (pin "2") (pinfunction "2_2") (pintype "passive"))
      (node (ref "C19") (pin "2") (pinfunction "2_2") (pintype "passive"))
      (node (ref "C2") (pin "2") (pinfunction "2_2") (pintype "passive"))
      (node (ref "C20") (pin "1") (pinfunction "1_1") (pintype "passive"))
      (node (ref "C21") (pin "1") (pinfunction "1_1") (pintype "passive"))
      (node (ref "C22") (pin "1") (pinfunction "1_1") (pintype "passive"))
      (node (ref "C23") (pin "1") (pinfunction "1_1") (pintype "passive"))
      (node (ref "C24") (pin "1") (pinfunction "1_1") (pintype "passive"))
      (node (ref "C25") (pin "1") (pinfunction "1_1") (pintype "passive"))
      (node (ref "C28") (pin "1") (pinfunction "1_1") (pintype "passive"))
      (node (ref "C29") (pin "1") (pinfunction "1_1") (pintype "passive"))
      (node (ref "C3") (pin "1") (pinfunction "1_1") (pintype "passive"))
      (node (ref "C30") (pin "2") (pinfunction "2_2") (pintype "passive"))
      (node (ref "C31") (pin "1") (pinfunction "1_1") (pintype "passive"))
      (node (ref "C4") (pin "2") (pinfunction "2_2") (pintype "passive"))
      (node (ref "C5") (pin "1") (pinfunction "1_1") (pintype "passive"))
      (node (ref "C6") (pin "2") (pinfunction "2_2") (pintype "passive"))
      (node (ref "C7") (pin "2") (pinfunction "2_2") (pintype "passive"))
      (node (ref "C8") (pin "2") (pinfunction "2_2") (pintype "passive"))
      (node (ref "C9") (pin "2") (pinfunction "2_2") (pintype "passive"))
      (node (ref "D26") (pin "3") (pinfunction "VSS_3") (pintype "passive"))
      (node (ref "D26") (pin "8") (pinfunction "VSS_8") (pintype "passive"))
      (node (ref "D27") (pin "2") (pinfunction "2_2") (pintype "passive"))
      (node (ref "D28") (pin "A") (pinfunction "A_A") (pintype "passive"))
      (node (ref "D29") (pin "3") (pinfunction "VSS_3") (pintype "passive"))
      (node (ref "D29") (pin "8") (pinfunction "VSS_8") (pintype "passive"))
      (node (ref "D30") (pin "3") (pinfunction "VSS_3") (pintype "passive"))
      (node (ref "D30") (pin "8") (pinfunction "VSS_8") (pintype "passive"))
      (node (ref "J8") (pin "10") (pintype "passive"))
      (node (ref "J8") (pin "11") (pintype "passive"))
      (node (ref "J8") (pin "16") (pintype "passive"))
      (node (ref "J8") (pin "3") (pintype "passive"))
      (node (ref "J8") (pin "4") (pintype "passive"))
      (node (ref "MEC1") (pin "1") (pintype "passive"))
      (node (ref "MEC2") (pin "1") (pintype "passive"))
      (node (ref "MTH5") (pin "1") (pinfunction "1_1") (pintype "passive"))
      (node (ref "MTH6") (pin "1") (pinfunction "1_1") (pintype "passive"))
      (node (ref "R122") (pin "2") (pinfunction "2_2") (pintype "passive"))
      (node (ref "R176") (pin "2") (pinfunction "2_2") (pintype "passive"))
      (node (ref "R9") (pin "1") (pinfunction "1_1") (pintype "passive"))
      (node (ref "U1") (pin "104") (pinfunction "VSS_104") (pintype "passive"))
      (node (ref "U1") (pin "118") (pinfunction "VSS_118") (pintype "passive"))
      (node (ref "U1") (pin "12") (pinfunction "VSS_12") (pintype "passive"))
      (node (ref "U1") (pin "128") (pinfunction "VSS_128") (pintype "passive"))
      (node (ref "U1") (pin "14") (pinfunction "VSSSMPS_14") (pintype "passive"))
      (node (ref "U1") (pin "141") (pinfunction "VSS_141") (pintype "passive"))
      (node (ref "U1") (pin "16") (pinfunction "VDDSMPS_16") (pintype "passive"))
      (node (ref "U1") (pin "17") (pinfunction "VFBSMPS_17") (pintype "passive"))
      (node (ref "U1") (pin "18") (pinfunction "VSS_18") (pintype "passive"))
      (node (ref "U1") (pin "33") (pinfunction "VSS_33") (pintype "passive"))
      (node (ref "U1") (pin "34") (pinfunction "VSSA_34") (pintype "passive"))
      (node (ref "U1") (pin "41") (pinfunction "VSS_41") (pintype "passive"))
      (node (ref "U1") (pin "55") (pinfunction "VSS_55") (pintype "passive"))
      (node (ref "U1") (pin "6") (pinfunction "VSS_6") (pintype "passive"))
      (node (ref "U1") (pin "69") (pinfunction "VSS_69") (pintype "passive"))
      (node (ref "U1") (pin "80") (pinfunction "VSS_80") (pintype "passive"))
      (node (ref "U1") (pin "89") (pinfunction "VSS_89") (pintype "passive"))
      (node (ref "X4") (pin "2") (pinfunction "GND_2") (pintype "passive"))
    )
    (net (code "105") (name "Net-(C4-Pad1)") (class "Default")
      (node (ref "C4") (pin "1") (pinfunction "1_1") (pintype "passive"))
      (node (ref "R8") (pin "1") (pinfunction "1_1") (pintype "passive"))
      (node (ref "S3") (pin "3") (pinfunction "3_3") (pintype "passive"))
      (node (ref "S3") (pin "4") (pinfunction "4_4") (pintype "passive"))
    )
    (net (code "106") (name "Net-(D1-B)") (class "Default")
      (node (ref "D1") (pin "1") (pinfunction "B_1") (pintype "passive"))
      (node (ref "R1") (pin "1") (pinfunction "1_1") (pintype "passive"))
    )
    (net (code "107") (name "Net-(D1-G)") (class "Default")
      (node (ref "D1") (pin "2") (pinfunction "G_2") (pintype "passive"))
      (node (ref "R2") (pin "1") (pinfunction "1_1") (pintype "passive"))
    )
    (net (code "108") (name "Net-(D1-R)") (class "Default")
      (node (ref "D1") (pin "4") (pinfunction "R_4") (pintype "passive"))
      (node (ref "R3") (pin "1") (pinfunction "1_1") (pintype "passive"))
    )
    (net (code "109") (name "Net-(D22-PadA)") (class "Default")
      (node (ref "D22") (pin "A") (pinfunction "A_A") (pintype "passive"))
      (node (ref "R5") (pin "2") (pinfunction "2_2") (pintype "passive"))
    )
    (net (code "110") (name "Net-(D23-PadA)") (class "Default")
      (node (ref "D23") (pin "A") (pinfunction "A_A") (pintype "passive"))
      (node (ref "R23") (pin "2") (pinfunction "2_2") (pintype "passive"))
    )
    (net (code "111") (name "Net-(D24-PadA)") (class "Default")
      (node (ref "D24") (pin "A") (pinfunction "A_A") (pintype "passive"))
      (node (ref "R33") (pin "2") (pinfunction "2_2") (pintype "passive"))
    )
    (net (code "112") (name "Net-(D25-PadA)") (class "Default")
      (node (ref "D25") (pin "A") (pinfunction "A_A") (pintype "passive"))
      (node (ref "R129") (pin "2") (pinfunction "2_2") (pintype "passive"))
    )
    (net (code "113") (name "Net-(R9-Pad2)") (class "Default")
      (node (ref "R9") (pin "2") (pinfunction "2_2") (pintype "passive"))
      (node (ref "S3") (pin "1") (pinfunction "1_1") (pintype "passive"))
      (node (ref "S3") (pin "2") (pinfunction "2_2") (pintype "passive"))
    )
    (net (code "114") (name "Net-(U1A-BOOT0)") (class "Default")
      (node (ref "R116") (pin "2") (pinfunction "2_2") (pintype "passive"))
      (node (ref "R122") (pin "1") (pinfunction "1_1") (pintype "passive"))
      (node (ref "U1") (pin "135") (pinfunction "BOOT0_135") (pintype "passive"))
    )
    (net (code "115") (name "Net-(U1A-PDR_ON)") (class "Default")
      (node (ref "R175") (pin "1") (pinfunction "1_1") (pintype "passive"))
      (node (ref "R176") (pin "1") (pinfunction "1_1") (pintype "passive"))
      (node (ref "U1") (pin "142") (pinfunction "PDR_ON_142") (pintype "passive"))
    )
    (net (code "116") (name "Net-(U1A-VREF+)") (class "Default")
      (node (ref "R130") (pin "2") (pinfunction "2_2") (pintype "passive"))
      (node (ref "U1") (pin "35") (pinfunction "VREF+_35") (pintype "passive"))
    )
    (net (code "117") (name "Net-(U1B-PB10)") (class "Default")
      (node (ref "R162") (pin "2") (pinfunction "2_2") (pintype "passive"))
      (node (ref "U1") (pin "66") (pinfunction "PB10_66") (pintype "passive"))
    )
    (net (code "118") (name "Net-(U1B-PB12)") (class "Default")
      (node (ref "R165") (pin "2") (pinfunction "2_2") (pintype "passive"))
      (node (ref "U1") (pin "72") (pinfunction "PB12_72") (pintype "passive"))
    )
    (net (code "119") (name "Net-(U1B-PB13)") (class "Default")
      (node (ref "R167") (pin "2") (pinfunction "2_2") (pintype "passive"))
      (node (ref "U1") (pin "73") (pinfunction "PB13_73") (pintype "passive"))
    )
    (net (code "120") (name "Net-(U1B-PB15)") (class "Default")
      (node (ref "R168") (pin "2") (pinfunction "2_2") (pintype "passive"))
      (node (ref "U1") (pin "75") (pinfunction "PB15_75") (pintype "passive"))
    )
    (net (code "121") (name "Net-(U1C-PC10)") (class "Default")
      (node (ref "R163") (pin "1") (pinfunction "1_1") (pintype "passive"))
      (node (ref "U1") (pin "109") (pinfunction "PC10_109") (pintype "passive"))
    )
    (net (code "122") (name "Net-(U1C-PC12)") (class "Default")
      (node (ref "R166") (pin "1") (pinfunction "1_1") (pintype "passive"))
      (node (ref "U1") (pin "111") (pinfunction "PC12_111") (pintype "passive"))
    )
    (net (code "123") (name "Net-(U1C-PD7)") (class "Default")
      (node (ref "R161") (pin "2") (pinfunction "2_2") (pintype "passive"))
      (node (ref "U1") (pin "121") (pinfunction "PD7_121") (pintype "passive"))
    )
    (net (code "124") (name "Net-(U1D-PE12)") (class "Default")
      (node (ref "R172") (pin "1") (pinfunction "1_1") (pintype "passive"))
      (node (ref "U1") (pin "62") (pinfunction "PE12_62") (pintype "passive"))
    )
    (net (code "125") (name "Net-(U1D-PE14)") (class "Default")
      (node (ref "R173") (pin "1") (pinfunction "1_1") (pintype "passive"))
      (node (ref "U1") (pin "64") (pinfunction "PE14_64") (pintype "passive"))
    )
    (net (code "126") (name "Net-(U1D-PF7)") (class "Default")
      (node (ref "R169") (pin "2") (pinfunction "2_2") (pintype "passive"))
      (node (ref "U1") (pin "21") (pinfunction "PF7_21") (pintype "passive"))
    )
    (net (code "127") (name "Net-(U1D-PF9)") (class "Default")
      (node (ref "R170") (pin "2") (pinfunction "2_2") (pintype "passive"))
      (node (ref "U1") (pin "23") (pinfunction "PF9_23") (pintype "passive"))
    )
    (net (code "128") (name "Net-(U1E-PG11)") (class "Default")
      (node (ref "R171") (pin "1") (pinfunction "1_1") (pintype "passive"))
      (node (ref "U1") (pin "124") (pinfunction "PG11_124") (pintype "passive"))
    )
    (net (code "129") (name "Net-(U1E-PH0-OSC_IN)") (class "Default")
      (node (ref "R178") (pin "2") (pinfunction "2_2") (pintype "passive"))
      (node (ref "U1") (pin "25") (pinfunction "PH0-OSC_IN_25") (pintype "passive"))
    )
    (net (code "130") (name "Net-(X4-OUTPUT)") (class "Default")
      (node (ref "R178") (pin "1") (pinfunction "1_1") (pintype "passive"))
      (node (ref "X4") (pin "3") (pinfunction "OUTPUT_3") (pintype "passive"))
    )
    (net (code "131") (name "unconnected-(D26-IO4-Pad5)") (class "Default")
      (node (ref "D26") (pin "5") (pinfunction "IO4_5") (pintype "passive+no_connect"))
    )
    (net (code "132") (name "unconnected-(D26-NC-Pad6)") (class "Default")
      (node (ref "D26") (pin "6") (pinfunction "NC_6") (pintype "passive+no_connect"))
    )
    (net (code "133") (name "unconnected-(D29-IO3-Pad4)") (class "Default")
      (node (ref "D29") (pin "4") (pinfunction "IO3_4") (pintype "passive+no_connect"))
    )
    (net (code "134") (name "unconnected-(D29-IO4-Pad5)") (class "Default")
      (node (ref "D29") (pin "5") (pinfunction "IO4_5") (pintype "passive+no_connect"))
    )
    (net (code "135") (name "unconnected-(D29-NC-Pad6)") (class "Default")
      (node (ref "D29") (pin "6") (pinfunction "NC_6") (pintype "passive+no_connect"))
    )
    (net (code "136") (name "unconnected-(D29-NC-Pad7)") (class "Default")
      (node (ref "D29") (pin "7") (pinfunction "NC_7") (pintype "passive+no_connect"))
    )
    (net (code "137") (name "unconnected-(U1A-VLXSMPS-Pad15)") (class "Default")
      (node (ref "U1") (pin "15") (pinfunction "VLXSMPS_15") (pintype "passive+no_connect"))
    )
    (net (code "138") (name "unconnected-(U1E-PH0-OSC_OUT-Pad26)") (class "Default")
      (node (ref "U1") (pin "26") (pinfunction "PH0-OSC_OUT_26") (pintype "passive+no_connect"))
    )
  )
)
